# LCD.net
KiCad netlist of a schematic drawn in Altium Designer
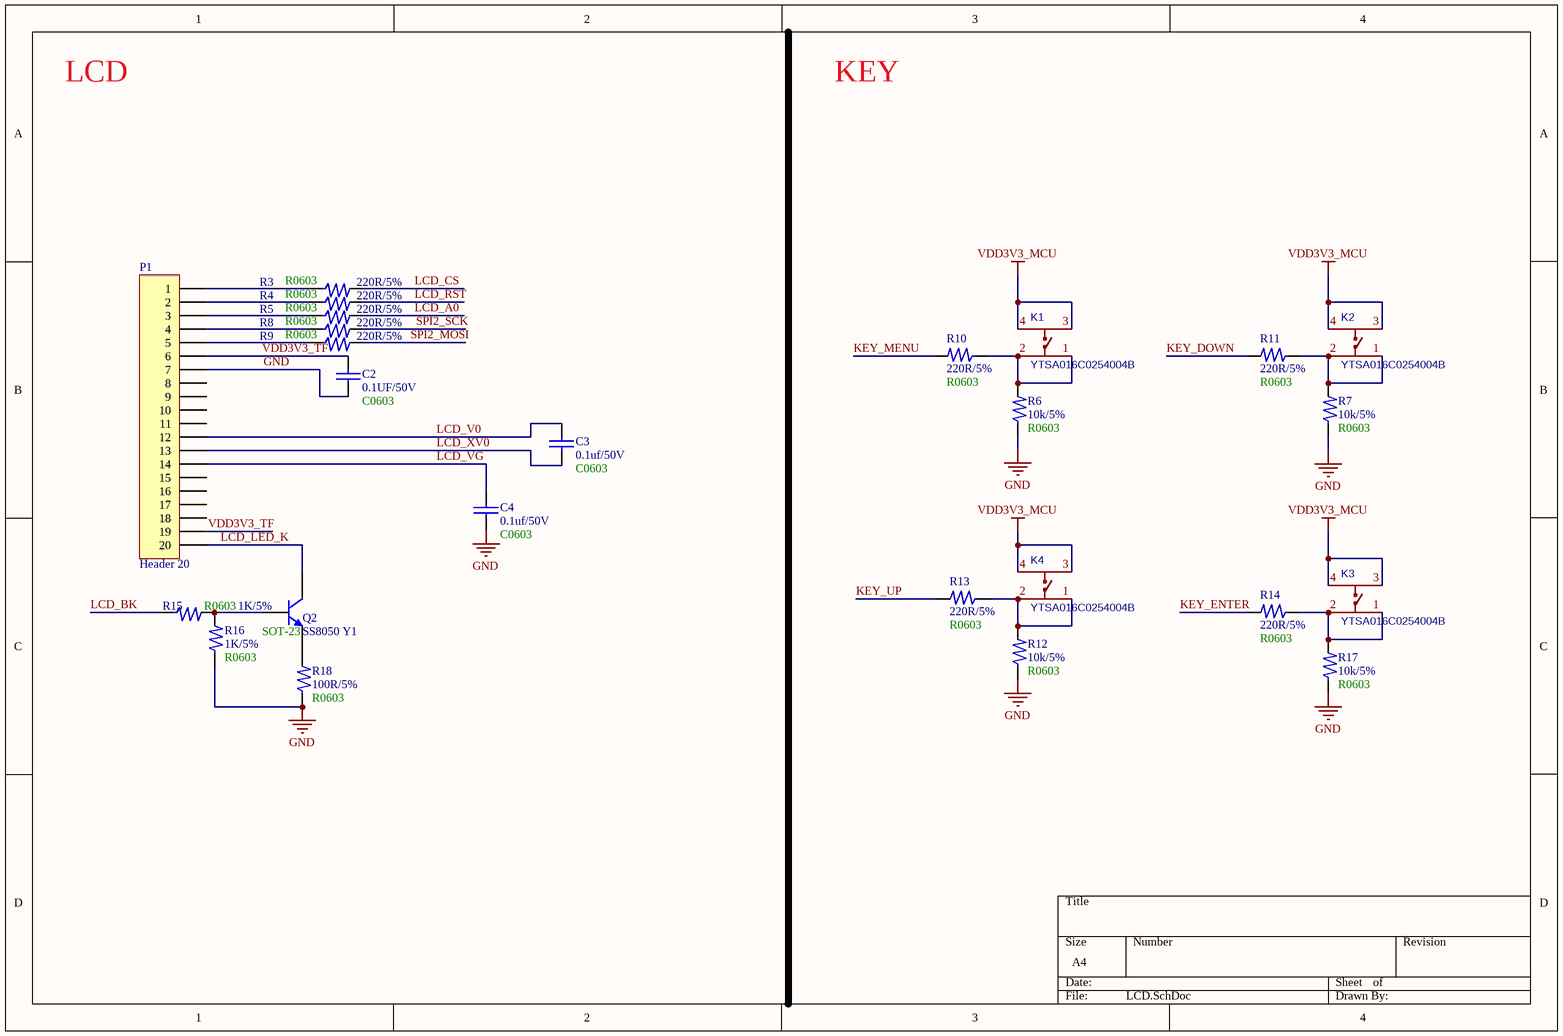
[diagram p0: LCD.SchDoc]

(export (version "E")
  (design (tool "Eeschema 10.0.6"))
  (components
    (comp (ref "C2")
      (value "0.1UF/50V")
      (footprint "C0603")
      (description "Capacitor")
      (libsource (lib "*") (part "CAP"))
    )
    (comp (ref "C3")
      (value "0.1uf/50V")
      (footprint "C0603")
      (description "Capacitor")
      (libsource (lib "*") (part "CAP"))
    )
    (comp (ref "C4")
      (value "0.1uf/50V")
      (footprint "C0603")
      (description "Capacitor")
      (libsource (lib "*") (part "CAP"))
    )
    (comp (ref "K1")
      (value "YTSA016C0254004B")
      (footprint "SMD6*6*4.5")
      (fields (field (name "BOM_SUPPLIER PART") "C2764970") (field (name "CONTRIBUTOR") "LCSC"))
      (libsource (lib "altium-import") (part "root_2_YTSA016C0254004B_"))
    )
    (comp (ref "K2")
      (value "YTSA016C0254004B")
      (footprint "SMD6*6*4.5")
      (fields (field (name "BOM_SUPPLIER PART") "C2764970") (field (name "CONTRIBUTOR") "LCSC"))
      (libsource (lib "altium-import") (part "root_2_YTSA016C0254004B_"))
    )
    (comp (ref "K3")
      (value "YTSA016C0254004B")
      (footprint "SMD6*6*4.5")
      (fields (field (name "BOM_SUPPLIER PART") "C2764970") (field (name "CONTRIBUTOR") "LCSC"))
      (libsource (lib "altium-import") (part "root_2_YTSA016C0254004B_"))
    )
    (comp (ref "K4")
      (value "YTSA016C0254004B")
      (footprint "SMD6*6*4.5")
      (fields (field (name "BOM_SUPPLIER PART") "C2764970") (field (name "CONTRIBUTOR") "LCSC"))
      (libsource (lib "altium-import") (part "root_2_YTSA016C0254004B_"))
    )
    (comp (ref "P1")
      (value "Header 20")
      (footprint "LCD")
      (description "Header, 20-Pin")
      (fields (field (name "PUBLISHER") "Altium Limited"))
      (libsource (lib "Miscellaneous Connectors") (part "Header 20"))
    )
    (comp (ref "Q2")
      (value "SS8050 Y1")
      (footprint "SOT-23(SOT-23-3)")
      (description "三极管")
      (fields (field (name "PACKAGE") "SOT-23"))
      (libsource (lib "Miscellaneous Devices LC") (part "SOT-23 SS8050 Y1"))
    )
    (comp (ref "R3") (value "220R/5%") (footprint "R0603") (libsource (lib "*") (part "电阻")))
    (comp (ref "R4") (value "220R/5%") (footprint "R0603") (libsource (lib "*") (part "电阻")))
    (comp (ref "R5") (value "220R/5%") (footprint "R0603") (libsource (lib "*") (part "电阻")))
    (comp (ref "R6") (value "10k/5%") (footprint "R0603") (libsource (lib "*") (part "电阻")))
    (comp (ref "R7") (value "10k/5%") (footprint "R0603") (libsource (lib "*") (part "电阻")))
    (comp (ref "R8") (value "220R/5%") (footprint "R0603") (libsource (lib "*") (part "电阻")))
    (comp (ref "R9") (value "220R/5%") (footprint "R0603") (libsource (lib "*") (part "电阻")))
    (comp (ref "R10") (value "220R/5%") (footprint "R0603") (libsource (lib "*") (part "电阻")))
    (comp (ref "R11") (value "220R/5%") (footprint "R0603") (libsource (lib "*") (part "电阻")))
    (comp (ref "R12") (value "10k/5%") (footprint "R0603") (libsource (lib "*") (part "电阻")))
    (comp (ref "R13") (value "220R/5%") (footprint "R0603") (libsource (lib "*") (part "电阻")))
    (comp (ref "R14") (value "220R/5%") (footprint "R0603") (libsource (lib "*") (part "电阻")))
    (comp (ref "R15") (value "1K/5%") (footprint "R0603") (libsource (lib "*") (part "电阻")))
    (comp (ref "R16") (value "1K/5%") (footprint "R0603") (libsource (lib "*") (part "电阻")))
    (comp (ref "R17") (value "10k/5%") (footprint "R0603") (libsource (lib "*") (part "电阻")))
    (comp (ref "R18") (value "100R/5%") (footprint "R0603") (libsource (lib "*") (part "电阻")))
  )
  (nets
    (net (code "1") (name "/KEY_DOWN") (class "Default") (node (ref "R11") (pin "1") (pintype "passive")))
    (net (code "2") (name "/KEY_ENTER") (class "Default") (node (ref "R14") (pin "1") (pintype "passive")))
    (net (code "3") (name "/KEY_MENU") (class "Default") (node (ref "R10") (pin "1") (pintype "passive")))
    (net (code "4") (name "/KEY_UP") (class "Default") (node (ref "R13") (pin "1") (pintype "passive")))
    (net (code "5") (name "/LCD_A0") (class "Default") (node (ref "R5") (pin "1") (pintype "passive")))
    (net (code "6") (name "/LCD_BK") (class "Default") (node (ref "R15") (pin "2") (pintype "passive")))
    (net (code "7") (name "/LCD_CS") (class "Default") (node (ref "R3") (pin "1") (pintype "passive")))
    (net (code "8") (name "/LCD_LED_K") (class "Default")
      (node (ref "P1") (pin "20") (pinfunction "20_20") (pintype "passive"))
      (node (ref "Q2") (pin "3") (pinfunction "C_3") (pintype "passive"))
    )
    (net (code "9") (name "/LCD_RST") (class "Default") (node (ref "R4") (pin "1") (pintype "passive")))
    (net (code "10") (name "/LCD_V0") (class "Default")
      (node (ref "C3") (pin "1") (pinfunction "1_1") (pintype "passive"))
      (node (ref "P1") (pin "12") (pinfunction "12_12") (pintype "passive"))
    )
    (net (code "11") (name "/LCD_VG") (class "Default")
      (node (ref "C4") (pin "1") (pinfunction "1_1") (pintype "passive"))
      (node (ref "P1") (pin "14") (pinfunction "14_14") (pintype "passive"))
    )
    (net (code "12") (name "/LCD_XV0") (class "Default")
      (node (ref "C3") (pin "2") (pinfunction "2_2") (pintype "passive"))
      (node (ref "P1") (pin "13") (pinfunction "13_13") (pintype "passive"))
    )
    (net (code "13") (name "/SPI2_MOSI") (class "Default") (node (ref "R9") (pin "1") (pintype "passive")))
    (net (code "14") (name "/SPI2_SCK") (class "Default") (node (ref "R8") (pin "1") (pintype "passive")))
    (net (code "15") (name "/VDD3V3_TF") (class "Default")
      (node (ref "C2") (pin "2") (pinfunction "2_2") (pintype "passive"))
      (node (ref "P1") (pin "19") (pinfunction "19_19") (pintype "passive"))
      (node (ref "P1") (pin "6") (pinfunction "6_6") (pintype "passive"))
    )
    (net (code "16") (name "GND") (class "Default")
      (node (ref "C2") (pin "1") (pinfunction "1_1") (pintype "passive"))
      (node (ref "C4") (pin "2") (pinfunction "2_2") (pintype "passive"))
      (node (ref "P1") (pin "7") (pinfunction "7_7") (pintype "passive"))
      (node (ref "R12") (pin "2") (pintype "passive"))
      (node (ref "R16") (pin "2") (pintype "passive"))
      (node (ref "R17") (pin "2") (pintype "passive"))
      (node (ref "R18") (pin "2") (pintype "passive"))
      (node (ref "R6") (pin "2") (pintype "passive"))
      (node (ref "R7") (pin "2") (pintype "passive"))
    )
    (net (code "17") (name "Net-(K1-Pad1)") (class "Default")
      (node (ref "K1") (pin "1") (pinfunction "1_1") (pintype "passive"))
      (node (ref "K1") (pin "2") (pinfunction "2_2") (pintype "passive"))
      (node (ref "R10") (pin "2") (pintype "passive"))
      (node (ref "R6") (pin "1") (pintype "passive"))
    )
    (net (code "18") (name "Net-(K2-Pad1)") (class "Default")
      (node (ref "K2") (pin "1") (pinfunction "1_1") (pintype "passive"))
      (node (ref "K2") (pin "2") (pinfunction "2_2") (pintype "passive"))
      (node (ref "R11") (pin "2") (pintype "passive"))
      (node (ref "R7") (pin "1") (pintype "passive"))
    )
    (net (code "19") (name "Net-(K3-Pad1)") (class "Default")
      (node (ref "K3") (pin "1") (pinfunction "1_1") (pintype "passive"))
      (node (ref "K3") (pin "2") (pinfunction "2_2") (pintype "passive"))
      (node (ref "R14") (pin "2") (pintype "passive"))
      (node (ref "R17") (pin "1") (pintype "passive"))
    )
    (net (code "20") (name "Net-(K4-Pad1)") (class "Default")
      (node (ref "K4") (pin "1") (pinfunction "1_1") (pintype "passive"))
      (node (ref "K4") (pin "2") (pinfunction "2_2") (pintype "passive"))
      (node (ref "R12") (pin "1") (pintype "passive"))
      (node (ref "R13") (pin "2") (pintype "passive"))
    )
    (net (code "21") (name "Net-(P1-Pad1)") (class "Default")
      (node (ref "P1") (pin "1") (pinfunction "1_1") (pintype "passive"))
      (node (ref "R3") (pin "2") (pintype "passive"))
    )
    (net (code "22") (name "Net-(P1-Pad2)") (class "Default")
      (node (ref "P1") (pin "2") (pinfunction "2_2") (pintype "passive"))
      (node (ref "R4") (pin "2") (pintype "passive"))
    )
    (net (code "23") (name "Net-(P1-Pad3)") (class "Default")
      (node (ref "P1") (pin "3") (pinfunction "3_3") (pintype "passive"))
      (node (ref "R5") (pin "2") (pintype "passive"))
    )
    (net (code "24") (name "Net-(P1-Pad4)") (class "Default")
      (node (ref "P1") (pin "4") (pinfunction "4_4") (pintype "passive"))
      (node (ref "R8") (pin "2") (pintype "passive"))
    )
    (net (code "25") (name "Net-(P1-Pad5)") (class "Default")
      (node (ref "P1") (pin "5") (pinfunction "5_5") (pintype "passive"))
      (node (ref "R9") (pin "2") (pintype "passive"))
    )
    (net (code "26") (name "Net-(Q2-B)") (class "Default")
      (node (ref "Q2") (pin "1") (pinfunction "B_1") (pintype "passive"))
      (node (ref "R15") (pin "1") (pintype "passive"))
      (node (ref "R16") (pin "1") (pintype "passive"))
    )
    (net (code "27") (name "Net-(Q2-E)") (class "Default")
      (node (ref "Q2") (pin "2") (pinfunction "E_2") (pintype "passive"))
      (node (ref "R18") (pin "1") (pintype "passive"))
    )
    (net (code "28") (name "VDD3V3_MCU") (class "Default")
      (node (ref "K1") (pin "3") (pinfunction "3_3") (pintype "passive"))
      (node (ref "K1") (pin "4") (pinfunction "4_4") (pintype "passive"))
      (node (ref "K2") (pin "3") (pinfunction "3_3") (pintype "passive"))
      (node (ref "K2") (pin "4") (pinfunction "4_4") (pintype "passive"))
      (node (ref "K3") (pin "3") (pinfunction "3_3") (pintype "passive"))
      (node (ref "K3") (pin "4") (pinfunction "4_4") (pintype "passive"))
      (node (ref "K4") (pin "3") (pinfunction "3_3") (pintype "passive"))
      (node (ref "K4") (pin "4") (pinfunction "4_4") (pintype "passive"))
    )
    (net (code "29") (name "unconnected-(P1-Pad8)") (class "Default")
      (node (ref "P1") (pin "8") (pinfunction "8_8") (pintype "passive"))
    )
    (net (code "30") (name "unconnected-(P1-Pad9)") (class "Default")
      (node (ref "P1") (pin "9") (pinfunction "9_9") (pintype "passive"))
    )
    (net (code "31") (name "unconnected-(P1-Pad10)") (class "Default")
      (node (ref "P1") (pin "10") (pinfunction "10_10") (pintype "passive"))
    )
    (net (code "32") (name "unconnected-(P1-Pad11)") (class "Default")
      (node (ref "P1") (pin "11") (pinfunction "11_11") (pintype "passive"))
    )
    (net (code "33") (name "unconnected-(P1-Pad15)") (class "Default")
      (node (ref "P1") (pin "15") (pinfunction "15_15") (pintype "passive"))
    )
    (net (code "34") (name "unconnected-(P1-Pad16)") (class "Default")
      (node (ref "P1") (pin "16") (pinfunction "16_16") (pintype "passive"))
    )
    (net (code "35") (name "unconnected-(P1-Pad17)") (class "Default")
      (node (ref "P1") (pin "17") (pinfunction "17_17") (pintype "passive"))
    )
    (net (code "36") (name "unconnected-(P1-Pad18)") (class "Default")
      (node (ref "P1") (pin "18") (pinfunction "18_18") (pintype "passive"))
    )
  )
)
